# GR_Action_Ascensseur.net
KiCad netlist of a schematic drawn in Altium Designer
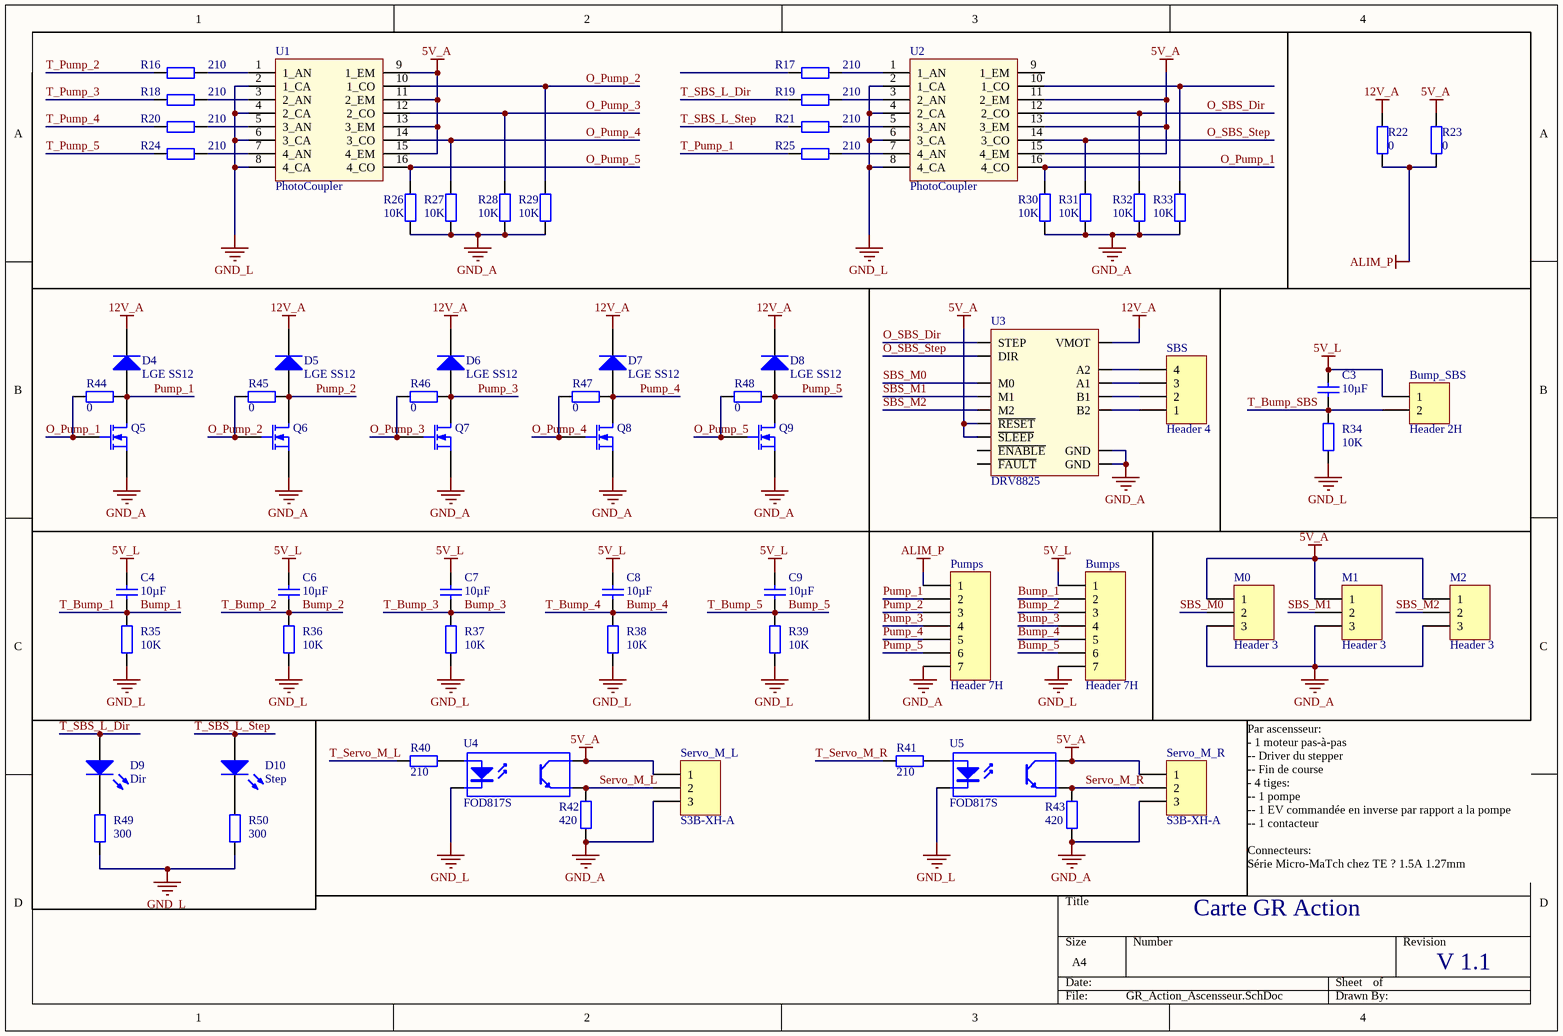
[diagram p0: GR_Action_Ascensseur.SchDoc]

(export (version "E")
  (design (tool "Eeschema 10.0.6"))
  (components
    (comp (ref "Bumps")
      (value "Header 7H")
      (footprint "S7B-XH-A")
      (description "Header, 7-Pin, Right Angle")
      (fields (field (name "PUBLISHER") "Altium Limited"))
      (libsource (lib "Miscellaneous Connectors") (part "Header 7H"))
    )
    (comp (ref "Bump_SBS")
      (value "Header 2H")
      (footprint "S2B-XH-A")
      (description "Header, 2-Pin, Right Angle")
      (fields (field (name "PUBLISHER") "Altium Limited"))
      (libsource (lib "Miscellaneous Connectors") (part "Header 2H"))
    )
    (comp (ref "C3")
      (value "10µF")
      (footprint "Capacitor 1206")
      (description "Capacitor")
      (fields (field (name "PUBLISHER") "Altium Limited"))
      (libsource (lib "Miscellaneous Devices") (part "Cap"))
    )
    (comp (ref "C4")
      (value "10µF")
      (footprint "Capacitor 1206")
      (description "Capacitor")
      (fields (field (name "PUBLISHER") "Altium Limited"))
      (libsource (lib "Miscellaneous Devices") (part "Cap"))
    )
    (comp (ref "C6")
      (value "10µF")
      (footprint "Capacitor 1206")
      (description "Capacitor")
      (fields (field (name "PUBLISHER") "Altium Limited"))
      (libsource (lib "Miscellaneous Devices") (part "Cap"))
    )
    (comp (ref "C7")
      (value "10µF")
      (footprint "Capacitor 1206")
      (description "Capacitor")
      (fields (field (name "PUBLISHER") "Altium Limited"))
      (libsource (lib "Miscellaneous Devices") (part "Cap"))
    )
    (comp (ref "C8")
      (value "10µF")
      (footprint "Capacitor 1206")
      (description "Capacitor")
      (fields (field (name "PUBLISHER") "Altium Limited"))
      (libsource (lib "Miscellaneous Devices") (part "Cap"))
    )
    (comp (ref "C9")
      (value "10µF")
      (footprint "Capacitor 1206")
      (description "Capacitor")
      (fields (field (name "PUBLISHER") "Altium Limited"))
      (libsource (lib "Miscellaneous Devices") (part "Cap"))
    )
    (comp (ref "D4")
      (value "LGE SS12")
      (footprint "SMB")
      (description "Default Diode")
      (fields (field (name "PUBLISHER") "Altium Limited"))
      (libsource (lib "Miscellaneous Devices") (part "Diode"))
    )
    (comp (ref "D5")
      (value "LGE SS12")
      (footprint "SMB")
      (description "Default Diode")
      (fields (field (name "PUBLISHER") "Altium Limited"))
      (libsource (lib "Miscellaneous Devices") (part "Diode"))
    )
    (comp (ref "D6")
      (value "LGE SS12")
      (footprint "SMB")
      (description "Default Diode")
      (fields (field (name "PUBLISHER") "Altium Limited"))
      (libsource (lib "Miscellaneous Devices") (part "Diode"))
    )
    (comp (ref "D7")
      (value "LGE SS12")
      (footprint "SMB")
      (description "Default Diode")
      (fields (field (name "PUBLISHER") "Altium Limited"))
      (libsource (lib "Miscellaneous Devices") (part "Diode"))
    )
    (comp (ref "D8")
      (value "LGE SS12")
      (footprint "SMB")
      (description "Default Diode")
      (fields (field (name "PUBLISHER") "Altium Limited"))
      (libsource (lib "Miscellaneous Devices") (part "Diode"))
    )
    (comp (ref "D9")
      (value "Dir")
      (footprint "KP-3216SEC")
      (description "Typical RED, GREEN, YELLOW, AMBER GaAs LED")
      (fields (field (name "PUBLISHER") "Altium Limited"))
      (libsource (lib "Miscellaneous Devices") (part "LED2"))
    )
    (comp (ref "D10")
      (value "Step")
      (footprint "KP-3216SEC")
      (description "Typical RED, GREEN, YELLOW, AMBER GaAs LED")
      (fields (field (name "PUBLISHER") "Altium Limited"))
      (libsource (lib "Miscellaneous Devices") (part "LED2"))
    )
    (comp (ref "M0")
      (value "Header 3")
      (footprint "HDR1X3")
      (description "Header, 3-Pin")
      (fields (field (name "PUBLISHER") "Altium Limited"))
      (libsource (lib "Miscellaneous Connectors") (part "Header 3"))
    )
    (comp (ref "M1")
      (value "Header 3")
      (footprint "HDR1X3")
      (description "Header, 3-Pin")
      (fields (field (name "PUBLISHER") "Altium Limited"))
      (libsource (lib "Miscellaneous Connectors") (part "Header 3"))
    )
    (comp (ref "M2")
      (value "Header 3")
      (footprint "HDR1X3")
      (description "Header, 3-Pin")
      (fields (field (name "PUBLISHER") "Altium Limited"))
      (libsource (lib "Miscellaneous Connectors") (part "Header 3"))
    )
    (comp (ref "Pumps")
      (value "Header 7H")
      (footprint "S7B-XH-A")
      (description "Header, 7-Pin, Right Angle")
      (fields (field (name "PUBLISHER") "Altium Limited"))
      (libsource (lib "Miscellaneous Connectors") (part "Header 7H"))
    )
    (comp (ref "Q5")
      (value "MOSFET-N")
      (footprint "SOT23_M")
      (description "N-Channel MOSFET")
      (fields (field (name "PUBLISHER") "Altium Limited"))
      (libsource (lib "Miscellaneous Devices") (part "MOSFET-N"))
    )
    (comp (ref "Q6")
      (value "MOSFET-N")
      (footprint "SOT23_M")
      (description "N-Channel MOSFET")
      (fields (field (name "PUBLISHER") "Altium Limited"))
      (libsource (lib "Miscellaneous Devices") (part "MOSFET-N"))
    )
    (comp (ref "Q7")
      (value "MOSFET-N")
      (footprint "SOT23_M")
      (description "N-Channel MOSFET")
      (fields (field (name "PUBLISHER") "Altium Limited"))
      (libsource (lib "Miscellaneous Devices") (part "MOSFET-N"))
    )
    (comp (ref "Q8")
      (value "MOSFET-N")
      (footprint "SOT23_M")
      (description "N-Channel MOSFET")
      (fields (field (name "PUBLISHER") "Altium Limited"))
      (libsource (lib "Miscellaneous Devices") (part "MOSFET-N"))
    )
    (comp (ref "Q9")
      (value "MOSFET-N")
      (footprint "SOT23_M")
      (description "N-Channel MOSFET")
      (fields (field (name "PUBLISHER") "Altium Limited"))
      (libsource (lib "Miscellaneous Devices") (part "MOSFET-N"))
    )
    (comp (ref "R16")
      (value "210")
      (footprint "Resistor 1206")
      (description "Resistor")
      (fields (field (name "Comment") "Res2") (field (name "PUBLISHER") "Altium Limited"))
      (libsource (lib "") (part "Res2_1"))
    )
    (comp (ref "R17")
      (value "210")
      (footprint "Resistor 1206")
      (description "Resistor")
      (fields (field (name "Comment") "Res2") (field (name "PUBLISHER") "Altium Limited"))
      (libsource (lib "") (part "Res2_1"))
    )
    (comp (ref "R18")
      (value "210")
      (footprint "Resistor 1206")
      (description "Resistor")
      (fields (field (name "Comment") "Res2") (field (name "PUBLISHER") "Altium Limited"))
      (libsource (lib "") (part "Res2_1"))
    )
    (comp (ref "R19")
      (value "210")
      (footprint "Resistor 1206")
      (description "Resistor")
      (fields (field (name "Comment") "Res2") (field (name "PUBLISHER") "Altium Limited"))
      (libsource (lib "") (part "Res2_1"))
    )
    (comp (ref "R20")
      (value "210")
      (footprint "Resistor 1206")
      (description "Resistor")
      (fields (field (name "Comment") "Res2") (field (name "PUBLISHER") "Altium Limited"))
      (libsource (lib "") (part "Res2_1"))
    )
    (comp (ref "R21")
      (value "210")
      (footprint "Resistor 1206")
      (description "Resistor")
      (fields (field (name "Comment") "Res2") (field (name "PUBLISHER") "Altium Limited"))
      (libsource (lib "") (part "Res2_1"))
    )
    (comp (ref "R22")
      (value "0")
      (footprint "Resistor 1206")
      (description "Resistor")
      (fields (field (name "Comment") "Res2") (field (name "PUBLISHER") "Altium Limited"))
      (libsource (lib "") (part "Res2_2"))
    )
    (comp (ref "R23")
      (value "0")
      (footprint "Resistor 1206")
      (description "Resistor")
      (fields (field (name "Comment") "Res2") (field (name "PUBLISHER") "Altium Limited"))
      (libsource (lib "") (part "Res2_2"))
    )
    (comp (ref "R24")
      (value "210")
      (footprint "Resistor 1206")
      (description "Resistor")
      (fields (field (name "Comment") "Res2") (field (name "PUBLISHER") "Altium Limited"))
      (libsource (lib "") (part "Res2_1"))
    )
    (comp (ref "R25")
      (value "210")
      (footprint "Resistor 1206")
      (description "Resistor")
      (fields (field (name "Comment") "Res2") (field (name "PUBLISHER") "Altium Limited"))
      (libsource (lib "") (part "Res2_1"))
    )
    (comp (ref "R26")
      (value "10K")
      (footprint "Resistor 1206")
      (description "Resistor")
      (fields (field (name "Comment") "Res2") (field (name "PUBLISHER") "Altium Limited"))
      (libsource (lib "Miscellaneous Devices") (part "Res2"))
    )
    (comp (ref "R27")
      (value "10K")
      (footprint "Resistor 1206")
      (description "Resistor")
      (fields (field (name "Comment") "Res2") (field (name "PUBLISHER") "Altium Limited"))
      (libsource (lib "Miscellaneous Devices") (part "Res2"))
    )
    (comp (ref "R28")
      (value "10K")
      (footprint "Resistor 1206")
      (description "Resistor")
      (fields (field (name "Comment") "Res2") (field (name "PUBLISHER") "Altium Limited"))
      (libsource (lib "Miscellaneous Devices") (part "Res2"))
    )
    (comp (ref "R29")
      (value "10K")
      (footprint "Resistor 1206")
      (description "Resistor")
      (fields (field (name "Comment") "Res2") (field (name "PUBLISHER") "Altium Limited"))
      (libsource (lib "Miscellaneous Devices") (part "Res2"))
    )
    (comp (ref "R30")
      (value "10K")
      (footprint "Resistor 1206")
      (description "Resistor")
      (fields (field (name "Comment") "Res2") (field (name "PUBLISHER") "Altium Limited"))
      (libsource (lib "Miscellaneous Devices") (part "Res2"))
    )
    (comp (ref "R31")
      (value "10K")
      (footprint "Resistor 1206")
      (description "Resistor")
      (fields (field (name "Comment") "Res2") (field (name "PUBLISHER") "Altium Limited"))
      (libsource (lib "Miscellaneous Devices") (part "Res2"))
    )
    (comp (ref "R32")
      (value "10K")
      (footprint "Resistor 1206")
      (description "Resistor")
      (fields (field (name "Comment") "Res2") (field (name "PUBLISHER") "Altium Limited"))
      (libsource (lib "Miscellaneous Devices") (part "Res2"))
    )
    (comp (ref "R33")
      (value "10K")
      (footprint "Resistor 1206")
      (description "Resistor")
      (fields (field (name "Comment") "Res2") (field (name "PUBLISHER") "Altium Limited"))
      (libsource (lib "Miscellaneous Devices") (part "Res2"))
    )
    (comp (ref "R34")
      (value "10K")
      (footprint "Resistor 1206")
      (description "Resistor")
      (fields (field (name "Comment") "Res2") (field (name "PUBLISHER") "Altium Limited"))
      (libsource (lib "Miscellaneous Devices") (part "Res2"))
    )
    (comp (ref "R35")
      (value "10K")
      (footprint "Resistor 1206")
      (description "Resistor")
      (fields (field (name "Comment") "Res2") (field (name "PUBLISHER") "Altium Limited"))
      (libsource (lib "Miscellaneous Devices") (part "Res2"))
    )
    (comp (ref "R36")
      (value "10K")
      (footprint "Resistor 1206")
      (description "Resistor")
      (fields (field (name "Comment") "Res2") (field (name "PUBLISHER") "Altium Limited"))
      (libsource (lib "Miscellaneous Devices") (part "Res2"))
    )
    (comp (ref "R37")
      (value "10K")
      (footprint "Resistor 1206")
      (description "Resistor")
      (fields (field (name "Comment") "Res2") (field (name "PUBLISHER") "Altium Limited"))
      (libsource (lib "Miscellaneous Devices") (part "Res2"))
    )
    (comp (ref "R38")
      (value "10K")
      (footprint "Resistor 1206")
      (description "Resistor")
      (fields (field (name "Comment") "Res2") (field (name "PUBLISHER") "Altium Limited"))
      (libsource (lib "Miscellaneous Devices") (part "Res2"))
    )
    (comp (ref "R39")
      (value "10K")
      (footprint "Resistor 1206")
      (description "Resistor")
      (fields (field (name "Comment") "Res2") (field (name "PUBLISHER") "Altium Limited"))
      (libsource (lib "Miscellaneous Devices") (part "Res2"))
    )
    (comp (ref "R40")
      (value "210")
      (footprint "Resistor 1206")
      (description "Resistor")
      (fields (field (name "Comment") "Res2") (field (name "PUBLISHER") "Altium Limited"))
      (libsource (lib "") (part "Res2_1"))
    )
    (comp (ref "R41")
      (value "210")
      (footprint "Resistor 1206")
      (description "Resistor")
      (fields (field (name "Comment") "Res2") (field (name "PUBLISHER") "Altium Limited"))
      (libsource (lib "") (part "Res2_1"))
    )
    (comp (ref "R42")
      (value "420")
      (footprint "Resistor 1206")
      (description "Resistor")
      (fields (field (name "Comment") "Res2") (field (name "PUBLISHER") "Altium Limited"))
      (libsource (lib "Miscellaneous Devices") (part "Res2"))
    )
    (comp (ref "R43")
      (value "420")
      (footprint "Resistor 1206")
      (description "Resistor")
      (fields (field (name "Comment") "Res2") (field (name "PUBLISHER") "Altium Limited"))
      (libsource (lib "Miscellaneous Devices") (part "Res2"))
    )
    (comp (ref "R44")
      (value "0")
      (footprint "Resistor 1206")
      (description "Resistor")
      (fields (field (name "Comment") "Res2") (field (name "PUBLISHER") "Altium Limited"))
      (libsource (lib "") (part "Res2_3"))
    )
    (comp (ref "R45")
      (value "0")
      (footprint "Resistor 1206")
      (description "Resistor")
      (fields (field (name "Comment") "Res2") (field (name "PUBLISHER") "Altium Limited"))
      (libsource (lib "") (part "Res2_3"))
    )
    (comp (ref "R46")
      (value "0")
      (footprint "Resistor 1206")
      (description "Resistor")
      (fields (field (name "Comment") "Res2") (field (name "PUBLISHER") "Altium Limited"))
      (libsource (lib "") (part "Res2_3"))
    )
    (comp (ref "R47")
      (value "0")
      (footprint "Resistor 1206")
      (description "Resistor")
      (fields (field (name "Comment") "Res2") (field (name "PUBLISHER") "Altium Limited"))
      (libsource (lib "") (part "Res2_3"))
    )
    (comp (ref "R48")
      (value "0")
      (footprint "Resistor 1206")
      (description "Resistor")
      (fields (field (name "Comment") "Res2") (field (name "PUBLISHER") "Altium Limited"))
      (libsource (lib "") (part "Res2_3"))
    )
    (comp (ref "R49")
      (value "300")
      (footprint "Resistor 1206")
      (description "Resistor")
      (fields (field (name "Comment") "Res2") (field (name "PUBLISHER") "Altium Limited"))
      (libsource (lib "Miscellaneous Devices") (part "Res2"))
    )
    (comp (ref "R50")
      (value "300")
      (footprint "Resistor 1206")
      (description "Resistor")
      (fields (field (name "Comment") "Res2") (field (name "PUBLISHER") "Altium Limited"))
      (libsource (lib "Miscellaneous Devices") (part "Res2"))
    )
    (comp (ref "SBS")
      (value "Header 4")
      (footprint "S4B-XH-A")
      (description "Header, 4-Pin")
      (fields (field (name "PUBLISHER") "Altium Limited"))
      (libsource (lib "Miscellaneous Connectors") (part "Header 4"))
    )
    (comp (ref "Servo_M_L")
      (value "S3B-XH-A")
      (footprint "S3B-XH-A")
      (description "Header, 3-Pin, Right Angle")
      (fields (field (name "PUBLISHER") "Altium Limited"))
      (libsource (lib "Miscellaneous Connectors") (part "Header 3H"))
    )
    (comp (ref "Servo_M_R")
      (value "S3B-XH-A")
      (footprint "S3B-XH-A")
      (description "Header, 3-Pin, Right Angle")
      (fields (field (name "PUBLISHER") "Altium Limited"))
      (libsource (lib "Miscellaneous Connectors") (part "Header 3H"))
    )
    (comp (ref "U1")
      (value "PhotoCoupler")
      (footprint "LTV-247")
      (description "Integrated Circuit")
      (fields
        (field (name "MANUFACTURER_PART_NUMBER") "LTV-247")
        (field (name "MOUSER PART NUMBER") "859-LTV-247")
      )
      (libsource (lib "SamacSys") (part "LTV-247"))
    )
    (comp (ref "U2")
      (value "PhotoCoupler")
      (footprint "LTV-247")
      (description "Integrated Circuit")
      (fields
        (field (name "MANUFACTURER_PART_NUMBER") "LTV-247")
        (field (name "MOUSER PART NUMBER") "859-LTV-247")
      )
      (libsource (lib "SamacSys") (part "LTV-247"))
    )
    (comp (ref "U3")
      (value "DRV8825")
      (footprint "DRV8825")
      (description "Stepper Driver Module")
      (libsource (lib "SupaeroRobot") (part "DRV8825"))
    )
    (comp (ref "U4")
      (value "FOD817S")
      (footprint "SOP254P1016X385-4N")
      (description "4-Pin Phototransistor Optocoupler")
      (fields (field (name "PUBLISHER") "Altium Limited"))
      (libsource (lib "Miscellaneous Devices") (part "Optoisolator1"))
    )
    (comp (ref "U5")
      (value "FOD817S")
      (footprint "SOP254P1016X385-4N")
      (description "4-Pin Phototransistor Optocoupler")
      (fields (field (name "PUBLISHER") "Altium Limited"))
      (libsource (lib "Miscellaneous Devices") (part "Optoisolator1"))
    )
  )
  (nets
    (net (code "1") (name "/Bump_1") (class "Default")
      (node (ref "Bumps") (pin "2") (pinfunction "2_2") (pintype "passive"))
      (node (ref "C4") (pin "1") (pinfunction "1_1") (pintype "passive"))
      (node (ref "R35") (pin "2") (pinfunction "2_2") (pintype "passive"))
    )
    (net (code "2") (name "/Bump_2") (class "Default")
      (node (ref "Bumps") (pin "3") (pinfunction "3_3") (pintype "passive"))
      (node (ref "C6") (pin "1") (pinfunction "1_1") (pintype "passive"))
      (node (ref "R36") (pin "2") (pinfunction "2_2") (pintype "passive"))
    )
    (net (code "3") (name "/Bump_3") (class "Default")
      (node (ref "Bumps") (pin "4") (pinfunction "4_4") (pintype "passive"))
      (node (ref "C7") (pin "1") (pinfunction "1_1") (pintype "passive"))
      (node (ref "R37") (pin "2") (pinfunction "2_2") (pintype "passive"))
    )
    (net (code "4") (name "/Bump_4") (class "Default")
      (node (ref "Bumps") (pin "5") (pinfunction "5_5") (pintype "passive"))
      (node (ref "C8") (pin "1") (pinfunction "1_1") (pintype "passive"))
      (node (ref "R38") (pin "2") (pinfunction "2_2") (pintype "passive"))
    )
    (net (code "5") (name "/Bump_5") (class "Default")
      (node (ref "Bumps") (pin "6") (pinfunction "6_6") (pintype "passive"))
      (node (ref "C9") (pin "1") (pinfunction "1_1") (pintype "passive"))
      (node (ref "R39") (pin "2") (pinfunction "2_2") (pintype "passive"))
    )
    (net (code "6") (name "/O_Pump_1") (class "Default")
      (node (ref "Q5") (pin "2") (pinfunction "G_2") (pintype "passive"))
      (node (ref "R30") (pin "2") (pinfunction "2_2") (pintype "passive"))
      (node (ref "R44") (pin "1") (pinfunction "1_1") (pintype "passive"))
      (node (ref "U2") (pin "16") (pinfunction "4_CO_16") (pintype "passive"))
    )
    (net (code "7") (name "/O_Pump_2") (class "Default")
      (node (ref "Q6") (pin "2") (pinfunction "G_2") (pintype "passive"))
      (node (ref "R29") (pin "2") (pinfunction "2_2") (pintype "passive"))
      (node (ref "R45") (pin "1") (pinfunction "1_1") (pintype "passive"))
      (node (ref "U1") (pin "10") (pinfunction "1_CO_10") (pintype "passive"))
    )
    (net (code "8") (name "/O_Pump_3") (class "Default")
      (node (ref "Q7") (pin "2") (pinfunction "G_2") (pintype "passive"))
      (node (ref "R28") (pin "2") (pinfunction "2_2") (pintype "passive"))
      (node (ref "R46") (pin "1") (pinfunction "1_1") (pintype "passive"))
      (node (ref "U1") (pin "12") (pinfunction "2_CO_12") (pintype "passive"))
    )
    (net (code "9") (name "/O_Pump_4") (class "Default")
      (node (ref "Q8") (pin "2") (pinfunction "G_2") (pintype "passive"))
      (node (ref "R27") (pin "2") (pinfunction "2_2") (pintype "passive"))
      (node (ref "R47") (pin "1") (pinfunction "1_1") (pintype "passive"))
      (node (ref "U1") (pin "14") (pinfunction "3_CO_14") (pintype "passive"))
    )
    (net (code "10") (name "/O_Pump_5") (class "Default")
      (node (ref "Q9") (pin "2") (pinfunction "G_2") (pintype "passive"))
      (node (ref "R26") (pin "2") (pinfunction "2_2") (pintype "passive"))
      (node (ref "R48") (pin "1") (pinfunction "1_1") (pintype "passive"))
      (node (ref "U1") (pin "16") (pinfunction "4_CO_16") (pintype "passive"))
    )
    (net (code "11") (name "/O_SBS_Dir") (class "Default")
      (node (ref "R32") (pin "2") (pinfunction "2_2") (pintype "passive"))
      (node (ref "U2") (pin "12") (pinfunction "2_CO_12") (pintype "passive"))
      (node (ref "U3") (pin "7") (pinfunction "STEP_7") (pintype "passive"))
    )
    (net (code "12") (name "/O_SBS_Step") (class "Default")
      (node (ref "R31") (pin "2") (pinfunction "2_2") (pintype "passive"))
      (node (ref "U2") (pin "14") (pinfunction "3_CO_14") (pintype "passive"))
      (node (ref "U3") (pin "8") (pinfunction "DIR_8") (pintype "passive"))
    )
    (net (code "13") (name "/Pump_1") (class "Default")
      (node (ref "D4") (pin "1") (pinfunction "A_1") (pintype "passive"))
      (node (ref "Pumps") (pin "2") (pinfunction "2_2") (pintype "passive"))
      (node (ref "Q5") (pin "1") (pinfunction "D_1") (pintype "passive"))
      (node (ref "R44") (pin "2") (pinfunction "2_2") (pintype "passive"))
    )
    (net (code "14") (name "/Pump_2") (class "Default")
      (node (ref "D5") (pin "1") (pinfunction "A_1") (pintype "passive"))
      (node (ref "Pumps") (pin "3") (pinfunction "3_3") (pintype "passive"))
      (node (ref "Q6") (pin "1") (pinfunction "D_1") (pintype "passive"))
      (node (ref "R45") (pin "2") (pinfunction "2_2") (pintype "passive"))
    )
    (net (code "15") (name "/Pump_3") (class "Default")
      (node (ref "D6") (pin "1") (pinfunction "A_1") (pintype "passive"))
      (node (ref "Pumps") (pin "4") (pinfunction "4_4") (pintype "passive"))
      (node (ref "Q7") (pin "1") (pinfunction "D_1") (pintype "passive"))
      (node (ref "R46") (pin "2") (pinfunction "2_2") (pintype "passive"))
    )
    (net (code "16") (name "/Pump_4") (class "Default")
      (node (ref "D7") (pin "1") (pinfunction "A_1") (pintype "passive"))
      (node (ref "Pumps") (pin "5") (pinfunction "5_5") (pintype "passive"))
      (node (ref "Q8") (pin "1") (pinfunction "D_1") (pintype "passive"))
      (node (ref "R47") (pin "2") (pinfunction "2_2") (pintype "passive"))
    )
    (net (code "17") (name "/Pump_5") (class "Default")
      (node (ref "D8") (pin "1") (pinfunction "A_1") (pintype "passive"))
      (node (ref "Pumps") (pin "6") (pinfunction "6_6") (pintype "passive"))
      (node (ref "Q9") (pin "1") (pinfunction "D_1") (pintype "passive"))
      (node (ref "R48") (pin "2") (pinfunction "2_2") (pintype "passive"))
    )
    (net (code "18") (name "/SBS_M0") (class "Default")
      (node (ref "M0") (pin "2") (pinfunction "2_2") (pintype "passive"))
      (node (ref "U3") (pin "2") (pinfunction "M0_2") (pintype "passive"))
    )
    (net (code "19") (name "/SBS_M1") (class "Default")
      (node (ref "M1") (pin "2") (pinfunction "2_2") (pintype "passive"))
      (node (ref "U3") (pin "3") (pinfunction "M1_3") (pintype "passive"))
    )
    (net (code "20") (name "/SBS_M2") (class "Default")
      (node (ref "M2") (pin "2") (pinfunction "2_2") (pintype "passive"))
      (node (ref "U3") (pin "4") (pinfunction "M2_4") (pintype "passive"))
    )
    (net (code "21") (name "/Servo_M_L") (class "Default")
      (node (ref "R42") (pin "2") (pinfunction "2_2") (pintype "passive"))
      (node (ref "Servo_M_L") (pin "2") (pinfunction "2_2") (pintype "passive"))
      (node (ref "U4") (pin "3") (pinfunction "E_3") (pintype "passive"))
    )
    (net (code "22") (name "/Servo_M_R") (class "Default")
      (node (ref "R43") (pin "2") (pinfunction "2_2") (pintype "passive"))
      (node (ref "Servo_M_R") (pin "2") (pinfunction "2_2") (pintype "passive"))
      (node (ref "U5") (pin "3") (pinfunction "E_3") (pintype "passive"))
    )
    (net (code "23") (name "/T_Bump_SBS") (class "Default")
      (node (ref "Bump_SBS") (pin "2") (pinfunction "2_2") (pintype "passive"))
      (node (ref "C3") (pin "1") (pinfunction "1_1") (pintype "passive"))
      (node (ref "R34") (pin "2") (pinfunction "2_2") (pintype "passive"))
    )
    (net (code "24") (name "/T_Pump_1") (class "Default")
      (node (ref "R25") (pin "2") (pinfunction "2_2") (pintype "passive"))
    )
    (net (code "25") (name "/T_Pump_2") (class "Default")
      (node (ref "R16") (pin "2") (pinfunction "2_2") (pintype "passive"))
    )
    (net (code "26") (name "/T_Pump_3") (class "Default")
      (node (ref "R18") (pin "2") (pinfunction "2_2") (pintype "passive"))
    )
    (net (code "27") (name "/T_Pump_4") (class "Default")
      (node (ref "R20") (pin "2") (pinfunction "2_2") (pintype "passive"))
    )
    (net (code "28") (name "/T_Pump_5") (class "Default")
      (node (ref "R24") (pin "2") (pinfunction "2_2") (pintype "passive"))
    )
    (net (code "29") (name "/T_SBS_L_Dir") (class "Default")
      (node (ref "D9") (pin "1") (pinfunction "A_1") (pintype "passive"))
      (node (ref "R19") (pin "2") (pinfunction "2_2") (pintype "passive"))
    )
    (net (code "30") (name "/T_SBS_L_Step") (class "Default")
      (node (ref "D10") (pin "1") (pinfunction "A_1") (pintype "passive"))
      (node (ref "R21") (pin "2") (pinfunction "2_2") (pintype "passive"))
    )
    (net (code "31") (name "/T_Servo_M_L") (class "Default")
      (node (ref "R40") (pin "2") (pinfunction "2_2") (pintype "passive"))
    )
    (net (code "32") (name "/T_Servo_M_R") (class "Default")
      (node (ref "R41") (pin "2") (pinfunction "2_2") (pintype "passive"))
    )
    (net (code "33") (name "5V_A") (class "Default")
      (node (ref "M0") (pin "1") (pinfunction "1_1") (pintype "passive"))
      (node (ref "M1") (pin "1") (pinfunction "1_1") (pintype "passive"))
      (node (ref "M2") (pin "1") (pinfunction "1_1") (pintype "passive"))
      (node (ref "R23") (pin "1") (pinfunction "1_1") (pintype "passive"))
      (node (ref "Servo_M_L") (pin "1") (pinfunction "1_1") (pintype "passive"))
      (node (ref "Servo_M_R") (pin "1") (pinfunction "1_1") (pintype "passive"))
      (node (ref "U1") (pin "11") (pinfunction "2_EM_11") (pintype "passive"))
      (node (ref "U1") (pin "13") (pinfunction "3_EM_13") (pintype "passive"))
      (node (ref "U1") (pin "15") (pinfunction "4_EM_15") (pintype "passive"))
      (node (ref "U1") (pin "9") (pinfunction "1_EM_9") (pintype "passive"))
      (node (ref "U2") (pin "11") (pinfunction "2_EM_11") (pintype "passive"))
      (node (ref "U2") (pin "13") (pinfunction "3_EM_13") (pintype "passive"))
      (node (ref "U2") (pin "15") (pinfunction "4_EM_15") (pintype "passive"))
      (node (ref "U3") (pin "5") (pinfunction "~{RESET}_5") (pintype "passive"))
      (node (ref "U3") (pin "6") (pinfunction "~{SLEEP}_6") (pintype "passive"))
      (node (ref "U4") (pin "4") (pinfunction "C_4") (pintype "passive"))
      (node (ref "U5") (pin "4") (pinfunction "C_4") (pintype "passive"))
    )
    (net (code "34") (name "5V_L") (class "Default")
      (node (ref "Bump_SBS") (pin "1") (pinfunction "1_1") (pintype "passive"))
      (node (ref "Bumps") (pin "1") (pinfunction "1_1") (pintype "passive"))
      (node (ref "C3") (pin "2") (pinfunction "2_2") (pintype "passive"))
      (node (ref "C4") (pin "2") (pinfunction "2_2") (pintype "passive"))
      (node (ref "C6") (pin "2") (pinfunction "2_2") (pintype "passive"))
      (node (ref "C7") (pin "2") (pinfunction "2_2") (pintype "passive"))
      (node (ref "C8") (pin "2") (pinfunction "2_2") (pintype "passive"))
      (node (ref "C9") (pin "2") (pinfunction "2_2") (pintype "passive"))
    )
    (net (code "35") (name "12V_A") (class "Default")
      (node (ref "D4") (pin "2") (pinfunction "K_2") (pintype "passive"))
      (node (ref "D5") (pin "2") (pinfunction "K_2") (pintype "passive"))
      (node (ref "D6") (pin "2") (pinfunction "K_2") (pintype "passive"))
      (node (ref "D7") (pin "2") (pinfunction "K_2") (pintype "passive"))
      (node (ref "D8") (pin "2") (pinfunction "K_2") (pintype "passive"))
      (node (ref "R22") (pin "1") (pinfunction "1_1") (pintype "passive"))
      (node (ref "U3") (pin "16") (pinfunction "VMOT_16") (pintype "passive"))
    )
    (net (code "36") (name "ALIM_P") (class "Default")
      (node (ref "Pumps") (pin "1") (pinfunction "1_1") (pintype "passive"))
      (node (ref "R22") (pin "2") (pinfunction "2_2") (pintype "passive"))
      (node (ref "R23") (pin "2") (pinfunction "2_2") (pintype "passive"))
    )
    (net (code "37") (name "GND_A") (class "Default")
      (node (ref "M0") (pin "3") (pinfunction "3_3") (pintype "passive"))
      (node (ref "M1") (pin "3") (pinfunction "3_3") (pintype "passive"))
      (node (ref "M2") (pin "3") (pinfunction "3_3") (pintype "passive"))
      (node (ref "Pumps") (pin "7") (pinfunction "7_7") (pintype "passive"))
      (node (ref "Q5") (pin "3") (pinfunction "S_3") (pintype "passive"))
      (node (ref "Q6") (pin "3") (pinfunction "S_3") (pintype "passive"))
      (node (ref "Q7") (pin "3") (pinfunction "S_3") (pintype "passive"))
      (node (ref "Q8") (pin "3") (pinfunction "S_3") (pintype "passive"))
      (node (ref "Q9") (pin "3") (pinfunction "S_3") (pintype "passive"))
      (node (ref "R26") (pin "1") (pinfunction "1_1") (pintype "passive"))
      (node (ref "R27") (pin "1") (pinfunction "1_1") (pintype "passive"))
      (node (ref "R28") (pin "1") (pinfunction "1_1") (pintype "passive"))
      (node (ref "R29") (pin "1") (pinfunction "1_1") (pintype "passive"))
      (node (ref "R30") (pin "1") (pinfunction "1_1") (pintype "passive"))
      (node (ref "R31") (pin "1") (pinfunction "1_1") (pintype "passive"))
      (node (ref "R32") (pin "1") (pinfunction "1_1") (pintype "passive"))
      (node (ref "R33") (pin "1") (pinfunction "1_1") (pintype "passive"))
      (node (ref "R42") (pin "1") (pinfunction "1_1") (pintype "passive"))
      (node (ref "R43") (pin "1") (pinfunction "1_1") (pintype "passive"))
      (node (ref "Servo_M_L") (pin "3") (pinfunction "3_3") (pintype "passive"))
      (node (ref "Servo_M_R") (pin "3") (pinfunction "3_3") (pintype "passive"))
      (node (ref "U3") (pin "15") (pinfunction "GND_15") (pintype "passive"))
      (node (ref "U3") (pin "9") (pinfunction "GND_9") (pintype "passive"))
    )
    (net (code "38") (name "GND_L") (class "Default")
      (node (ref "Bumps") (pin "7") (pinfunction "7_7") (pintype "passive"))
      (node (ref "R34") (pin "1") (pinfunction "1_1") (pintype "passive"))
      (node (ref "R35") (pin "1") (pinfunction "1_1") (pintype "passive"))
      (node (ref "R36") (pin "1") (pinfunction "1_1") (pintype "passive"))
      (node (ref "R37") (pin "1") (pinfunction "1_1") (pintype "passive"))
      (node (ref "R38") (pin "1") (pinfunction "1_1") (pintype "passive"))
      (node (ref "R39") (pin "1") (pinfunction "1_1") (pintype "passive"))
      (node (ref "R49") (pin "1") (pinfunction "1_1") (pintype "passive"))
      (node (ref "R50") (pin "1") (pinfunction "1_1") (pintype "passive"))
      (node (ref "U1") (pin "2") (pinfunction "1_CA_2") (pintype "passive"))
      (node (ref "U1") (pin "4") (pinfunction "2_CA_4") (pintype "passive"))
      (node (ref "U1") (pin "6") (pinfunction "3_CA_6") (pintype "passive"))
      (node (ref "U1") (pin "8") (pinfunction "4_CA_8") (pintype "passive"))
      (node (ref "U2") (pin "2") (pinfunction "1_CA_2") (pintype "passive"))
      (node (ref "U2") (pin "4") (pinfunction "2_CA_4") (pintype "passive"))
      (node (ref "U2") (pin "6") (pinfunction "3_CA_6") (pintype "passive"))
      (node (ref "U2") (pin "8") (pinfunction "4_CA_8") (pintype "passive"))
      (node (ref "U4") (pin "2") (pinfunction "K_2") (pintype "passive"))
      (node (ref "U5") (pin "2") (pinfunction "K_2") (pintype "passive"))
    )
    (net (code "39") (name "Net-(D9-K)") (class "Default")
      (node (ref "D9") (pin "2") (pinfunction "K_2") (pintype "passive"))
      (node (ref "R49") (pin "2") (pinfunction "2_2") (pintype "passive"))
    )
    (net (code "40") (name "Net-(D10-K)") (class "Default")
      (node (ref "D10") (pin "2") (pinfunction "K_2") (pintype "passive"))
      (node (ref "R50") (pin "2") (pinfunction "2_2") (pintype "passive"))
    )
    (net (code "41") (name "Net-(U1-1_AN)") (class "Default")
      (node (ref "R16") (pin "1") (pinfunction "1_1") (pintype "passive"))
      (node (ref "U1") (pin "1") (pinfunction "1_AN_1") (pintype "passive"))
    )
    (net (code "42") (name "Net-(U1-2_AN)") (class "Default")
      (node (ref "R18") (pin "1") (pinfunction "1_1") (pintype "passive"))
      (node (ref "U1") (pin "3") (pinfunction "2_AN_3") (pintype "passive"))
    )
    (net (code "43") (name "Net-(U1-3_AN)") (class "Default")
      (node (ref "R20") (pin "1") (pinfunction "1_1") (pintype "passive"))
      (node (ref "U1") (pin "5") (pinfunction "3_AN_5") (pintype "passive"))
    )
    (net (code "44") (name "Net-(U1-4_AN)") (class "Default")
      (node (ref "R24") (pin "1") (pinfunction "1_1") (pintype "passive"))
      (node (ref "U1") (pin "7") (pinfunction "4_AN_7") (pintype "passive"))
    )
    (net (code "45") (name "Net-(U2-1_AN)") (class "Default")
      (node (ref "R17") (pin "1") (pinfunction "1_1") (pintype "passive"))
      (node (ref "U2") (pin "1") (pinfunction "1_AN_1") (pintype "passive"))
    )
    (net (code "46") (name "Net-(U2-1_CO)") (class "Default")
      (node (ref "R33") (pin "2") (pinfunction "2_2") (pintype "passive"))
      (node (ref "U2") (pin "10") (pinfunction "1_CO_10") (pintype "passive"))
    )
    (net (code "47") (name "Net-(U2-2_AN)") (class "Default")
      (node (ref "R19") (pin "1") (pinfunction "1_1") (pintype "passive"))
      (node (ref "U2") (pin "3") (pinfunction "2_AN_3") (pintype "passive"))
    )
    (net (code "48") (name "Net-(U2-3_AN)") (class "Default")
      (node (ref "R21") (pin "1") (pinfunction "1_1") (pintype "passive"))
      (node (ref "U2") (pin "5") (pinfunction "3_AN_5") (pintype "passive"))
    )
    (net (code "49") (name "Net-(U2-4_AN)") (class "Default")
      (node (ref "R25") (pin "1") (pinfunction "1_1") (pintype "passive"))
      (node (ref "U2") (pin "7") (pinfunction "4_AN_7") (pintype "passive"))
    )
    (net (code "50") (name "Net-(U3-A1)") (class "Default")
      (node (ref "SBS") (pin "3") (pinfunction "3_3") (pintype "passive"))
      (node (ref "U3") (pin "12") (pinfunction "A1_12") (pintype "passive"))
    )
    (net (code "51") (name "Net-(U3-A2)") (class "Default")
      (node (ref "SBS") (pin "4") (pinfunction "4_4") (pintype "passive"))
      (node (ref "U3") (pin "11") (pinfunction "A2_11") (pintype "passive"))
    )
    (net (code "52") (name "Net-(U3-B1)") (class "Default")
      (node (ref "SBS") (pin "2") (pinfunction "2_2") (pintype "passive"))
      (node (ref "U3") (pin "13") (pinfunction "B1_13") (pintype "passive"))
    )
    (net (code "53") (name "Net-(U3-B2)") (class "Default")
      (node (ref "SBS") (pin "1") (pinfunction "1_1") (pintype "passive"))
      (node (ref "U3") (pin "14") (pinfunction "B2_14") (pintype "passive"))
    )
    (net (code "54") (name "Net-(U4-A)") (class "Default")
      (node (ref "R40") (pin "1") (pinfunction "1_1") (pintype "passive"))
      (node (ref "U4") (pin "1") (pinfunction "A_1") (pintype "passive"))
    )
    (net (code "55") (name "Net-(U5-A)") (class "Default")
      (node (ref "R41") (pin "1") (pinfunction "1_1") (pintype "passive"))
      (node (ref "U5") (pin "1") (pinfunction "A_1") (pintype "passive"))
    )
    (net (code "56") (name "unconnected-(R17-Pad2)") (class "Default")
      (node (ref "R17") (pin "2") (pinfunction "2_2") (pintype "passive"))
    )
    (net (code "57") (name "unconnected-(U2-1_EM-Pad9)") (class "Default")
      (node (ref "U2") (pin "9") (pinfunction "1_EM_9") (pintype "passive"))
    )
    (net (code "58") (name "unconnected-(U3-~{ENABLE}-Pad1)") (class "Default")
      (node (ref "U3") (pin "1") (pinfunction "~{ENABLE}_1") (pintype "passive"))
    )
    (net (code "59") (name "unconnected-(U3-~{FAULT}-Pad10)") (class "Default")
      (node (ref "U3") (pin "10") (pinfunction "~{FAULT}_10") (pintype "passive"))
    )
  )
)
